# P2N-001.net
KiCad netlist of a schematic drawn in EAGLE
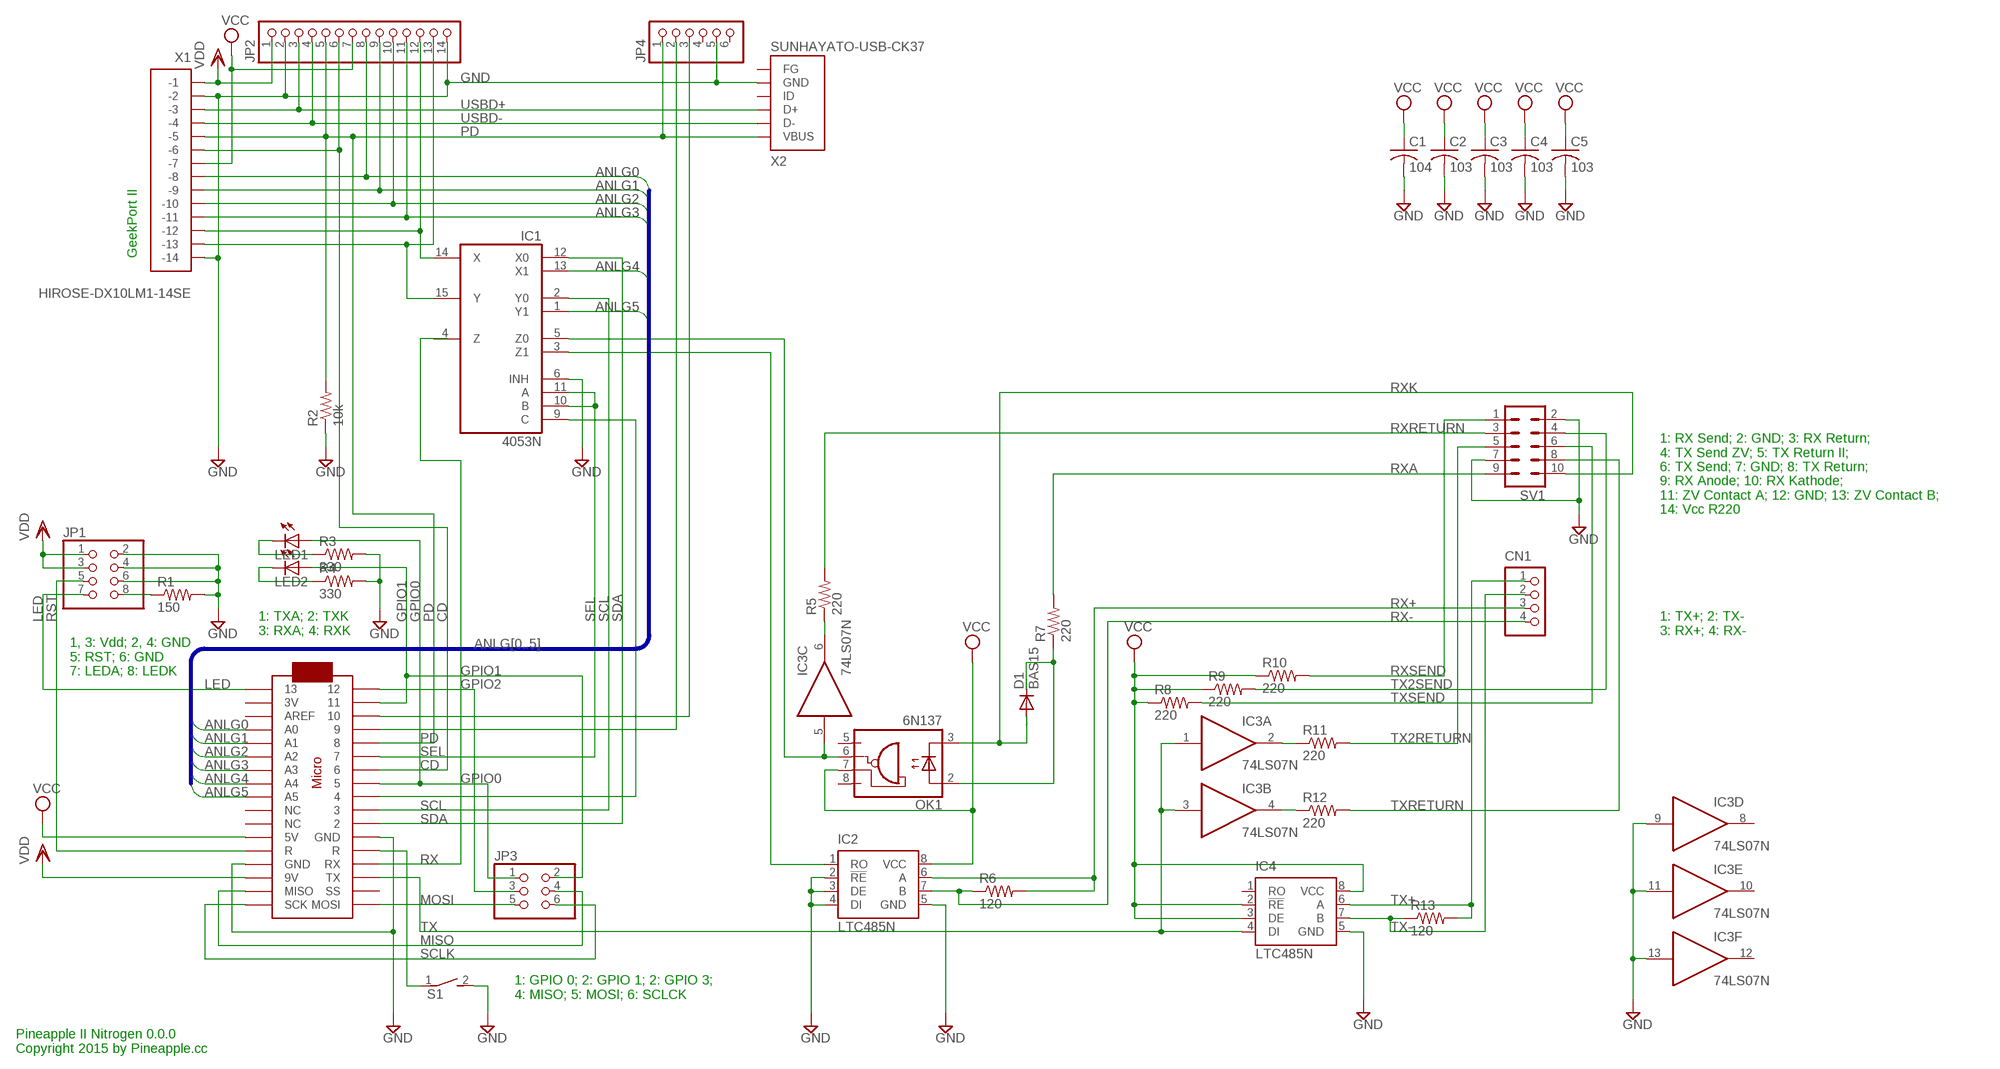
[diagram p0: schematic, sheet 1]

(export (version "E")
  (design (tool "Eeschema 10.0.6"))
  (components
    (comp (ref "C1")
      (value "104")
      (footprint "eagle-import:C025-025X050")
      (libsource (lib "eagle-import") (part "C-US025-025X050"))
    )
    (comp (ref "C2")
      (value "103")
      (footprint "eagle-import:C025-025X050")
      (libsource (lib "eagle-import") (part "C-US025-025X050"))
    )
    (comp (ref "C3")
      (value "103")
      (footprint "eagle-import:C025-025X050")
      (libsource (lib "eagle-import") (part "C-US025-025X050"))
    )
    (comp (ref "C4")
      (value "103")
      (footprint "eagle-import:C025-025X050")
      (libsource (lib "eagle-import") (part "C-US025-025X050"))
    )
    (comp (ref "C5")
      (value "103")
      (footprint "eagle-import:C025-025X050")
      (libsource (lib "eagle-import") (part "C-US025-025X050"))
    )
    (comp (ref "CN1")
      (value "S4B-PH-K-S")
      (footprint "eagle-import:S4B-PH-K-S")
      (libsource (lib "eagle-import") (part "S4B-PH-K-S"))
    )
    (comp (ref "D1")
      (value "BAS15")
      (footprint "eagle-import:DO34-7")
      (libsource (lib "eagle-import") (part "BAS15"))
    )
    (comp (ref "IC1")
      (value "4053N")
      (footprint "eagle-import:DIL16")
      (libsource (lib "eagle-import") (part "4053N"))
    )
    (comp (ref "IC2")
      (value "LTC485N")
      (footprint "eagle-import:DIL08")
      (libsource (lib "eagle-import") (part "LTC485N"))
    )
    (comp (ref "IC3")
      (value "74LS07N")
      (footprint "eagle-import:DIL14")
      (libsource (lib "eagle-import") (part "7407NLS"))
    )
    (comp (ref "IC4")
      (value "LTC485N")
      (footprint "eagle-import:DIL08")
      (libsource (lib "eagle-import") (part "LTC485N"))
    )
    (comp (ref "JP1")
      (value "PINHD-2X4")
      (footprint "eagle-import:2X04")
      (libsource (lib "eagle-import") (part "PINHD-2X4"))
    )
    (comp (ref "JP2")
      (value "PINHD-1X14-CB")
      (footprint "eagle-import:1X14-CB")
      (libsource (lib "eagle-import") (part "PINHD-1X14-CB"))
    )
    (comp (ref "JP3")
      (value "PINHD-2X3")
      (footprint "eagle-import:2X03")
      (libsource (lib "eagle-import") (part "PINHD-2X3"))
    )
    (comp (ref "JP4")
      (value "PINHD-1X6")
      (footprint "eagle-import:1X06")
      (libsource (lib "eagle-import") (part "PINHD-1X6"))
    )
    (comp (ref "LED1")
      (value "LED3MM")
      (footprint "eagle-import:LED3MM")
      (libsource (lib "eagle-import") (part "LED3MM"))
    )
    (comp (ref "LED2")
      (value "LED3MM")
      (footprint "eagle-import:LED3MM")
      (libsource (lib "eagle-import") (part "LED3MM"))
    )
    (comp (ref "MC1")
      (value "ARDUINOMICRO")
      (footprint "eagle-import:ARDUINOMICRO")
      (libsource (lib "eagle-import") (part "ARDUINOMICRO"))
    )
    (comp (ref "OK1")
      (value "6N137")
      (footprint "eagle-import:DIL08")
      (libsource (lib "eagle-import") (part "6N137"))
    )
    (comp (ref "R1")
      (value "150")
      (footprint "eagle-import:0204_5")
      (libsource (lib "eagle-import") (part "R-US_0204/5"))
    )
    (comp (ref "R2")
      (value "10k")
      (footprint "eagle-import:0204_5")
      (libsource (lib "eagle-import") (part "R-US_0204/5"))
    )
    (comp (ref "R3")
      (value "330")
      (footprint "eagle-import:0204_5")
      (libsource (lib "eagle-import") (part "R-US_0204/5"))
    )
    (comp (ref "R4")
      (value "330")
      (footprint "eagle-import:0204_5")
      (libsource (lib "eagle-import") (part "R-US_0204/5"))
    )
    (comp (ref "R5")
      (value "220")
      (footprint "eagle-import:0204_5")
      (libsource (lib "eagle-import") (part "R-US_0204/5"))
    )
    (comp (ref "R6")
      (value "120")
      (footprint "eagle-import:0204_5")
      (libsource (lib "eagle-import") (part "R-US_0204/5"))
    )
    (comp (ref "R7")
      (value "220")
      (footprint "eagle-import:0204_5")
      (libsource (lib "eagle-import") (part "R-US_0204/5"))
    )
    (comp (ref "R8")
      (value "220")
      (footprint "eagle-import:0204_5")
      (libsource (lib "eagle-import") (part "R-US_0204/5"))
    )
    (comp (ref "R9")
      (value "220")
      (footprint "eagle-import:0204_5")
      (libsource (lib "eagle-import") (part "R-US_0204/5"))
    )
    (comp (ref "R10")
      (value "220")
      (footprint "eagle-import:0204_5")
      (libsource (lib "eagle-import") (part "R-US_0204/5"))
    )
    (comp (ref "R11")
      (value "220")
      (footprint "eagle-import:0204_5")
      (libsource (lib "eagle-import") (part "R-US_0204/5"))
    )
    (comp (ref "R12")
      (value "220")
      (footprint "eagle-import:0204_5")
      (libsource (lib "eagle-import") (part "R-US_0204/5"))
    )
    (comp (ref "R13")
      (value "120")
      (footprint "eagle-import:0204_5")
      (libsource (lib "eagle-import") (part "R-US_0204/5"))
    )
    (comp (ref "S1")
      (value "DS01E")
      (footprint "eagle-import:DS-01")
      (libsource (lib "eagle-import") (part "DS01E"))
    )
    (comp (ref "SV1")
      (value "ML10L")
      (footprint "eagle-import:ML10L")
      (libsource (lib "eagle-import") (part "ML10L"))
    )
    (comp (ref "X1")
      (value "HIROSE-DX10LM1-14SE")
      (footprint "eagle-import:HIROSE-DX10LM1-14SE")
      (fields (field (name "MPN") "AXR30545"))
      (libsource (lib "eagle-import") (part "HIROSE-DX10LM1-14SE"))
    )
    (comp (ref "X2")
      (value "SUNHAYATO-USB-CK37")
      (footprint "eagle-import:SUNHAYATO-USB-CK37")
      (fields (field (name "MPN") "AXR30545"))
      (libsource (lib "eagle-import") (part "SUNHAYATO-USB-CK37"))
    )
  )
  (nets
    (net (code "1") (name "/ANLG0") (class "Default")
      (node (ref "JP2") (pin "8") (pinfunction "8_8") (pintype "passive"))
      (node (ref "MC1") (pin "P$31") (pinfunction "A0_P$31") (pintype "bidirectional"))
      (node (ref "X1") (pin "P$8") (pinfunction "-8_P$8") (pintype "input"))
    )
    (net (code "2") (name "/ANLG1") (class "Default")
      (node (ref "JP2") (pin "9") (pinfunction "9_9") (pintype "passive"))
      (node (ref "MC1") (pin "P$30") (pinfunction "A1_P$30") (pintype "bidirectional"))
      (node (ref "X1") (pin "P$9") (pinfunction "-9_P$9") (pintype "input"))
    )
    (net (code "3") (name "/ANLG2") (class "Default")
      (node (ref "JP2") (pin "10") (pinfunction "10_10") (pintype "passive"))
      (node (ref "MC1") (pin "P$29") (pinfunction "A2_P$29") (pintype "bidirectional"))
      (node (ref "X1") (pin "P$10") (pinfunction "-10_P$10") (pintype "input"))
    )
    (net (code "4") (name "/ANLG3") (class "Default")
      (node (ref "JP2") (pin "11") (pinfunction "11_11") (pintype "passive"))
      (node (ref "MC1") (pin "P$28") (pinfunction "A3_P$28") (pintype "bidirectional"))
      (node (ref "X1") (pin "P$11") (pinfunction "-11_P$11") (pintype "input"))
    )
    (net (code "5") (name "/ANLG4") (class "Default")
      (node (ref "IC1") (pin "13") (pinfunction "X1_13") (pintype "bidirectional"))
      (node (ref "MC1") (pin "P$27") (pinfunction "A4_P$27") (pintype "bidirectional"))
    )
    (net (code "6") (name "/ANLG5") (class "Default")
      (node (ref "IC1") (pin "1") (pinfunction "Y1_1") (pintype "bidirectional"))
      (node (ref "MC1") (pin "P$26") (pinfunction "A5_P$26") (pintype "bidirectional"))
    )
    (net (code "8") (name "/CD") (class "Default")
      (node (ref "JP2") (pin "6") (pinfunction "6_6") (pintype "passive"))
      (node (ref "MC1") (pin "P$7") (pinfunction "6_P$7") (pintype "bidirectional"))
      (node (ref "X1") (pin "P$6") (pinfunction "-6_P$6") (pintype "input"))
    )
    (net (code "9") (name "/GPIO0") (class "Default")
      (node (ref "JP3") (pin "1") (pinfunction "1_1") (pintype "passive"))
      (node (ref "LED1") (pin "A") (pinfunction "A_A") (pintype "passive"))
      (node (ref "MC1") (pin "P$8") (pinfunction "5_P$8") (pintype "bidirectional"))
    )
    (net (code "10") (name "/GPIO1") (class "Default")
      (node (ref "JP3") (pin "2") (pinfunction "2_2") (pintype "passive"))
      (node (ref "LED2") (pin "A") (pinfunction "A_A") (pintype "passive"))
      (node (ref "MC1") (pin "P$2") (pinfunction "11_P$2") (pintype "bidirectional"))
    )
    (net (code "11") (name "/GPIO2") (class "Default")
      (node (ref "JP3") (pin "3") (pinfunction "3_3") (pintype "passive"))
      (node (ref "MC1") (pin "P$1") (pinfunction "12_P$1") (pintype "bidirectional"))
    )
    (net (code "12") (name "/LED") (class "Default")
      (node (ref "JP1") (pin "7") (pinfunction "7_7") (pintype "passive"))
      (node (ref "MC1") (pin "P$34") (pinfunction "13_P$34") (pintype "bidirectional"))
    )
    (net (code "13") (name "/MISO") (class "Default")
      (node (ref "JP3") (pin "4") (pinfunction "4_4") (pintype "passive"))
      (node (ref "MC1") (pin "P$19") (pinfunction "MISO_P$19") (pintype "bidirectional"))
    )
    (net (code "14") (name "/MOSI") (class "Default")
      (node (ref "JP3") (pin "5") (pinfunction "5_5") (pintype "passive"))
      (node (ref "MC1") (pin "P$17") (pinfunction "MOSI_P$17") (pintype "bidirectional"))
    )
    (net (code "15") (name "/PD") (class "Default")
      (node (ref "JP2") (pin "5") (pinfunction "5_5") (pintype "passive"))
      (node (ref "JP4") (pin "1") (pinfunction "1_1") (pintype "passive"))
      (node (ref "MC1") (pin "P$5") (pinfunction "8_P$5") (pintype "bidirectional"))
      (node (ref "R2") (pin "2") (pinfunction "2_2") (pintype "passive"))
      (node (ref "X1") (pin "P$5") (pinfunction "-5_P$5") (pintype "input"))
      (node (ref "X2") (pin "P$1") (pinfunction "VBUS_P$1") (pintype "input"))
    )
    (net (code "16") (name "/RST") (class "Default")
      (node (ref "JP1") (pin "5") (pinfunction "5_5") (pintype "passive"))
      (node (ref "MC1") (pin "P$13") (pinfunction "R_P$13") (pintype "bidirectional"))
    )
    (net (code "17") (name "/RX") (class "Default")
      (node (ref "MC1") (pin "P$14") (pinfunction "RX_P$14") (pintype "bidirectional"))
    )
    (net (code "18") (name "/RX+") (class "Default")
      (node (ref "CN1") (pin "3") (pinfunction "3_3") (pintype "passive"))
      (node (ref "IC2") (pin "6") (pinfunction "A_6") (pintype "bidirectional"))
      (node (ref "R6") (pin "2") (pinfunction "2_2") (pintype "passive"))
    )
    (net (code "19") (name "/RX-") (class "Default")
      (node (ref "CN1") (pin "4") (pinfunction "4_4") (pintype "passive"))
      (node (ref "IC2") (pin "7") (pinfunction "B_7") (pintype "bidirectional"))
      (node (ref "R6") (pin "1") (pinfunction "1_1") (pintype "passive"))
    )
    (net (code "20") (name "/RXA") (class "Default")
      (node (ref "R7") (pin "2") (pinfunction "2_2") (pintype "passive"))
      (node (ref "SV1") (pin "9") (pinfunction "9_9") (pintype "passive"))
    )
    (net (code "21") (name "/RXK") (class "Default")
      (node (ref "D1") (pin "A") (pinfunction "A_A") (pintype "passive"))
      (node (ref "OK1") (pin "3") (pinfunction "C_3") (pintype "passive"))
      (node (ref "SV1") (pin "10") (pinfunction "10_10") (pintype "passive"))
    )
    (net (code "22") (name "/RXRETURN") (class "Default")
      (node (ref "R5") (pin "2") (pinfunction "2_2") (pintype "passive"))
      (node (ref "SV1") (pin "3") (pinfunction "3_3") (pintype "passive"))
    )
    (net (code "23") (name "/RXSEND") (class "Default")
      (node (ref "R10") (pin "2") (pinfunction "2_2") (pintype "passive"))
      (node (ref "SV1") (pin "1") (pinfunction "1_1") (pintype "passive"))
    )
    (net (code "24") (name "/SCL") (class "Default")
      (node (ref "IC1") (pin "2") (pinfunction "Y0_2") (pintype "bidirectional"))
      (node (ref "MC1") (pin "P$10") (pinfunction "3_P$10") (pintype "bidirectional"))
    )
    (net (code "25") (name "/SCLK") (class "Default")
      (node (ref "JP3") (pin "6") (pinfunction "6_6") (pintype "passive"))
      (node (ref "MC1") (pin "P$18") (pinfunction "SCK_P$18") (pintype "bidirectional"))
    )
    (net (code "26") (name "/SDA") (class "Default")
      (node (ref "IC1") (pin "12") (pinfunction "X0_12") (pintype "bidirectional"))
      (node (ref "MC1") (pin "P$11") (pinfunction "2_P$11") (pintype "bidirectional"))
    )
    (net (code "27") (name "/SEL") (class "Default")
      (node (ref "IC1") (pin "10") (pinfunction "B_10") (pintype "input"))
      (node (ref "IC1") (pin "11") (pinfunction "A_11") (pintype "input"))
      (node (ref "MC1") (pin "P$6") (pinfunction "7_P$6") (pintype "bidirectional"))
    )
    (net (code "28") (name "/TX") (class "Default")
      (node (ref "IC3") (pin "1") (pinfunction "I_1") (pintype "input"))
      (node (ref "IC3") (pin "3") (pinfunction "I_3") (pintype "input"))
      (node (ref "IC4") (pin "4") (pinfunction "DI_4") (pintype "input"))
      (node (ref "MC1") (pin "P$15") (pinfunction "TX_P$15") (pintype "bidirectional"))
    )
    (net (code "29") (name "/TX+") (class "Default")
      (node (ref "CN1") (pin "1") (pinfunction "1_1") (pintype "passive"))
      (node (ref "IC4") (pin "6") (pinfunction "A_6") (pintype "bidirectional"))
      (node (ref "R13") (pin "2") (pinfunction "2_2") (pintype "passive"))
    )
    (net (code "30") (name "/TX-") (class "Default")
      (node (ref "CN1") (pin "2") (pinfunction "2_2") (pintype "passive"))
      (node (ref "IC4") (pin "7") (pinfunction "B_7") (pintype "bidirectional"))
      (node (ref "R13") (pin "1") (pinfunction "1_1") (pintype "passive"))
    )
    (net (code "31") (name "/TX2RETURN") (class "Default")
      (node (ref "R11") (pin "2") (pinfunction "2_2") (pintype "passive"))
      (node (ref "SV1") (pin "5") (pinfunction "5_5") (pintype "passive"))
    )
    (net (code "32") (name "/TX2SEND") (class "Default")
      (node (ref "R9") (pin "2") (pinfunction "2_2") (pintype "passive"))
      (node (ref "SV1") (pin "4") (pinfunction "4_4") (pintype "passive"))
    )
    (net (code "33") (name "/TXRETURN") (class "Default")
      (node (ref "R12") (pin "2") (pinfunction "2_2") (pintype "passive"))
      (node (ref "SV1") (pin "8") (pinfunction "8_8") (pintype "passive"))
    )
    (net (code "34") (name "/TXSEND") (class "Default")
      (node (ref "R8") (pin "2") (pinfunction "2_2") (pintype "passive"))
      (node (ref "SV1") (pin "6") (pinfunction "6_6") (pintype "passive"))
    )
    (net (code "35") (name "/USBD+") (class "Default")
      (node (ref "JP2") (pin "3") (pinfunction "3_3") (pintype "passive"))
      (node (ref "X1") (pin "P$3") (pinfunction "-3_P$3") (pintype "input"))
      (node (ref "X2") (pin "P$3") (pinfunction "D+_P$3") (pintype "input"))
    )
    (net (code "36") (name "/USBD-") (class "Default")
      (node (ref "JP2") (pin "4") (pinfunction "4_4") (pintype "passive"))
      (node (ref "X1") (pin "P$4") (pinfunction "-4_P$4") (pintype "input"))
      (node (ref "X2") (pin "P$2") (pinfunction "D-_P$2") (pintype "input"))
    )
    (net (code "37") (name "GND") (class "Default")
      (node (ref "C1") (pin "2") (pinfunction "2_2") (pintype "passive"))
      (node (ref "C2") (pin "2") (pinfunction "2_2") (pintype "passive"))
      (node (ref "C3") (pin "2") (pinfunction "2_2") (pintype "passive"))
      (node (ref "C4") (pin "2") (pinfunction "2_2") (pintype "passive"))
      (node (ref "C5") (pin "2") (pinfunction "2_2") (pintype "passive"))
      (node (ref "IC1") (pin "6") (pinfunction "INH_6") (pintype "input"))
      (node (ref "IC2") (pin "2") (pinfunction "~{RE}_2") (pintype "input"))
      (node (ref "IC2") (pin "3") (pinfunction "DE_3") (pintype "input"))
      (node (ref "IC2") (pin "4") (pinfunction "DI_4") (pintype "input"))
      (node (ref "IC2") (pin "5") (pinfunction "GND_5") (pintype "input"))
      (node (ref "IC3") (pin "11") (pinfunction "I_11") (pintype "input"))
      (node (ref "IC3") (pin "13") (pinfunction "I_13") (pintype "input"))
      (node (ref "IC3") (pin "9") (pinfunction "I_9") (pintype "input"))
      (node (ref "IC4") (pin "5") (pinfunction "GND_5") (pintype "input"))
      (node (ref "JP1") (pin "2") (pinfunction "2_2") (pintype "passive"))
      (node (ref "JP1") (pin "4") (pinfunction "4_4") (pintype "passive"))
      (node (ref "JP1") (pin "6") (pinfunction "6_6") (pintype "passive"))
      (node (ref "JP2") (pin "14") (pinfunction "14_14") (pintype "passive"))
      (node (ref "JP2") (pin "2") (pinfunction "2_2") (pintype "passive"))
      (node (ref "JP4") (pin "5") (pinfunction "5_5") (pintype "passive"))
      (node (ref "MC1") (pin "P$12") (pinfunction "GND_P$12") (pintype "bidirectional"))
      (node (ref "MC1") (pin "P$21") (pinfunction "GND_P$21") (pintype "bidirectional"))
      (node (ref "R1") (pin "2") (pinfunction "2_2") (pintype "passive"))
      (node (ref "R2") (pin "1") (pinfunction "1_1") (pintype "passive"))
      (node (ref "R3") (pin "2") (pinfunction "2_2") (pintype "passive"))
      (node (ref "R4") (pin "2") (pinfunction "2_2") (pintype "passive"))
      (node (ref "S1") (pin "2") (pinfunction "2_2") (pintype "passive"))
      (node (ref "SV1") (pin "2") (pinfunction "2_2") (pintype "passive"))
      (node (ref "SV1") (pin "7") (pinfunction "7_7") (pintype "passive"))
      (node (ref "X1") (pin "P$14") (pinfunction "-14_P$14") (pintype "input"))
      (node (ref "X1") (pin "P$2") (pinfunction "-2_P$2") (pintype "input"))
      (node (ref "X2") (pin "P$5") (pinfunction "GND_P$5") (pintype "input"))
    )
    (net (code "38") (name "Net-(IC1A-C)") (class "Default")
      (node (ref "IC1") (pin "9") (pinfunction "C_9") (pintype "input"))
      (node (ref "MC1") (pin "P$9") (pinfunction "4_P$9") (pintype "bidirectional"))
    )
    (net (code "39") (name "Net-(IC1A-X)") (class "Default")
      (node (ref "IC1") (pin "14") (pinfunction "X_14") (pintype "bidirectional"))
      (node (ref "JP2") (pin "12") (pinfunction "12_12") (pintype "passive"))
      (node (ref "X1") (pin "P$12") (pinfunction "-12_P$12") (pintype "input"))
    )
    (net (code "40") (name "Net-(IC1A-Y)") (class "Default")
      (node (ref "IC1") (pin "15") (pinfunction "Y_15") (pintype "bidirectional"))
      (node (ref "JP2") (pin "13") (pinfunction "13_13") (pintype "passive"))
      (node (ref "X1") (pin "P$13") (pinfunction "-13_P$13") (pintype "input"))
    )
    (net (code "41") (name "Net-(IC1A-Z0)") (class "Default")
      (node (ref "IC1") (pin "5") (pinfunction "Z0_5") (pintype "bidirectional"))
      (node (ref "IC3") (pin "5") (pinfunction "I_5") (pintype "input"))
      (node (ref "OK1") (pin "6") (pinfunction "VO_6") (pintype "passive"))
    )
    (net (code "42") (name "Net-(IC1A-Z1)") (class "Default")
      (node (ref "IC1") (pin "3") (pinfunction "Z1_3") (pintype "bidirectional"))
      (node (ref "IC2") (pin "1") (pinfunction "RO_1") (pintype "output"))
    )
    (net (code "43") (name "Net-(IC3A-O)") (class "Default")
      (node (ref "IC3") (pin "2") (pinfunction "O_2") (pintype "open_collector"))
      (node (ref "R11") (pin "1") (pinfunction "1_1") (pintype "passive"))
    )
    (net (code "44") (name "Net-(IC3B-O)") (class "Default")
      (node (ref "IC3") (pin "4") (pinfunction "O_4") (pintype "open_collector"))
      (node (ref "R12") (pin "1") (pinfunction "1_1") (pintype "passive"))
    )
    (net (code "45") (name "Net-(IC3C-O)") (class "Default")
      (node (ref "IC3") (pin "6") (pinfunction "O_6") (pintype "open_collector"))
      (node (ref "R5") (pin "1") (pinfunction "1_1") (pintype "passive"))
    )
    (net (code "46") (name "Net-(JP1-Pad8)") (class "Default")
      (node (ref "JP1") (pin "8") (pinfunction "8_8") (pintype "passive"))
      (node (ref "R1") (pin "1") (pinfunction "1_1") (pintype "passive"))
    )
    (net (code "47") (name "Net-(LED1-C)") (class "Default")
      (node (ref "LED1") (pin "K") (pinfunction "C_K") (pintype "passive"))
      (node (ref "R3") (pin "1") (pinfunction "1_1") (pintype "passive"))
    )
    (net (code "48") (name "Net-(LED2-C)") (class "Default")
      (node (ref "LED2") (pin "K") (pinfunction "C_K") (pintype "passive"))
      (node (ref "R4") (pin "1") (pinfunction "1_1") (pintype "passive"))
    )
    (net (code "49") (name "Net-(MC1-9)") (class "Default")
      (node (ref "JP4") (pin "2") (pinfunction "2_2") (pintype "passive"))
      (node (ref "MC1") (pin "P$4") (pinfunction "9_P$4") (pintype "bidirectional"))
    )
    (net (code "50") (name "Net-(MC1-10)") (class "Default")
      (node (ref "JP4") (pin "3") (pinfunction "3_3") (pintype "passive"))
      (node (ref "MC1") (pin "P$3") (pinfunction "10_P$3") (pintype "bidirectional"))
    )
    (net (code "51") (name "Net-(MC1-R-PadP$22)") (class "Default")
      (node (ref "MC1") (pin "P$22") (pinfunction "R_P$22") (pintype "bidirectional"))
      (node (ref "S1") (pin "1") (pinfunction "1_1") (pintype "passive"))
    )
    (net (code "52") (name "Net-(OK1-A)") (class "Default")
      (node (ref "D1") (pin "C") (pinfunction "C_C") (pintype "passive"))
      (node (ref "OK1") (pin "2") (pinfunction "A_2") (pintype "passive"))
      (node (ref "R7") (pin "1") (pinfunction "1_1") (pintype "passive"))
    )
    (net (code "53") (name "VCC") (class "Default")
      (node (ref "C1") (pin "1") (pinfunction "1_1") (pintype "passive"))
      (node (ref "C2") (pin "1") (pinfunction "1_1") (pintype "passive"))
      (node (ref "C3") (pin "1") (pinfunction "1_1") (pintype "passive"))
      (node (ref "C4") (pin "1") (pinfunction "1_1") (pintype "passive"))
      (node (ref "C5") (pin "1") (pinfunction "1_1") (pintype "passive"))
      (node (ref "IC2") (pin "8") (pinfunction "VCC_8") (pintype "input"))
      (node (ref "IC4") (pin "2") (pinfunction "~{RE}_2") (pintype "input"))
      (node (ref "IC4") (pin "3") (pinfunction "DE_3") (pintype "input"))
      (node (ref "IC4") (pin "8") (pinfunction "VCC_8") (pintype "input"))
      (node (ref "JP2") (pin "7") (pinfunction "7_7") (pintype "passive"))
      (node (ref "MC1") (pin "P$23") (pinfunction "5V_P$23") (pintype "bidirectional"))
      (node (ref "OK1") (pin "7") (pinfunction "VE_7") (pintype "passive"))
      (node (ref "R10") (pin "1") (pinfunction "1_1") (pintype "passive"))
      (node (ref "R8") (pin "1") (pinfunction "1_1") (pintype "passive"))
      (node (ref "R9") (pin "1") (pinfunction "1_1") (pintype "passive"))
      (node (ref "X1") (pin "P$7") (pinfunction "-7_P$7") (pintype "input"))
    )
    (net (code "54") (name "VDD") (class "Default")
      (node (ref "JP1") (pin "1") (pinfunction "1_1") (pintype "passive"))
      (node (ref "JP1") (pin "3") (pinfunction "3_3") (pintype "passive"))
      (node (ref "JP2") (pin "1") (pinfunction "1_1") (pintype "passive"))
      (node (ref "MC1") (pin "P$20") (pinfunction "9V_P$20") (pintype "bidirectional"))
      (node (ref "X1") (pin "P$1") (pinfunction "-1_P$1") (pintype "input"))
    )
    (net (code "55") (name "unconnected-(IC1A-Z-Pad4)") (class "Default")
      (node (ref "IC1") (pin "4") (pinfunction "Z_4") (pintype "bidirectional"))
    )
    (net (code "56") (name "unconnected-(IC3D-O-Pad8)") (class "Default")
      (node (ref "IC3") (pin "8") (pinfunction "O_8") (pintype "open_collector"))
    )
    (net (code "57") (name "unconnected-(IC3E-O-Pad10)") (class "Default")
      (node (ref "IC3") (pin "10") (pinfunction "O_10") (pintype "open_collector"))
    )
    (net (code "58") (name "unconnected-(IC3F-O-Pad12)") (class "Default")
      (node (ref "IC3") (pin "12") (pinfunction "O_12") (pintype "open_collector"))
    )
    (net (code "59") (name "unconnected-(IC4-RO-Pad1)") (class "Default")
      (node (ref "IC4") (pin "1") (pinfunction "RO_1") (pintype "output"))
    )
    (net (code "60") (name "unconnected-(JP4-Pad4)") (class "Default")
      (node (ref "JP4") (pin "4") (pinfunction "4_4") (pintype "passive"))
    )
    (net (code "61") (name "unconnected-(JP4-Pad6)") (class "Default")
      (node (ref "JP4") (pin "6") (pinfunction "6_6") (pintype "passive"))
    )
    (net (code "62") (name "unconnected-(MC1-3V-PadP$33)") (class "Default")
      (node (ref "MC1") (pin "P$33") (pinfunction "3V_P$33") (pintype "bidirectional"))
    )
    (net (code "63") (name "unconnected-(MC1-AREF-PadP$32)") (class "Default")
      (node (ref "MC1") (pin "P$32") (pinfunction "AREF_P$32") (pintype "bidirectional"))
    )
    (net (code "64") (name "unconnected-(MC1-NC-PadP$24)") (class "Default")
      (node (ref "MC1") (pin "P$24") (pinfunction "NC_P$24") (pintype "bidirectional"))
    )
    (net (code "65") (name "unconnected-(MC1-NC-PadP$25)") (class "Default")
      (node (ref "MC1") (pin "P$25") (pinfunction "NC_P$25") (pintype "bidirectional"))
    )
    (net (code "66") (name "unconnected-(MC1-SS-PadP$16)") (class "Default")
      (node (ref "MC1") (pin "P$16") (pinfunction "SS_P$16") (pintype "bidirectional"))
    )
    (net (code "67") (name "unconnected-(OK1-GND-Pad5)") (class "Default")
      (node (ref "OK1") (pin "5") (pinfunction "GND_5") (pintype "passive"))
    )
    (net (code "68") (name "unconnected-(OK1-VCC-Pad8)") (class "Default")
      (node (ref "OK1") (pin "8") (pinfunction "VCC_8") (pintype "passive"))
    )
    (net (code "69") (name "unconnected-(X2-FG-PadP$6)") (class "Default")
      (node (ref "X2") (pin "P$6") (pinfunction "FG_P$6") (pintype "input"))
    )
    (net (code "70") (name "unconnected-(X2-ID-PadP$4)") (class "Default")
      (node (ref "X2") (pin "P$4") (pinfunction "ID_P$4") (pintype "input"))
    )
  )
)
